# wake_on_sleep.net
KiCad netlist of a schematic drawn in EAGLE
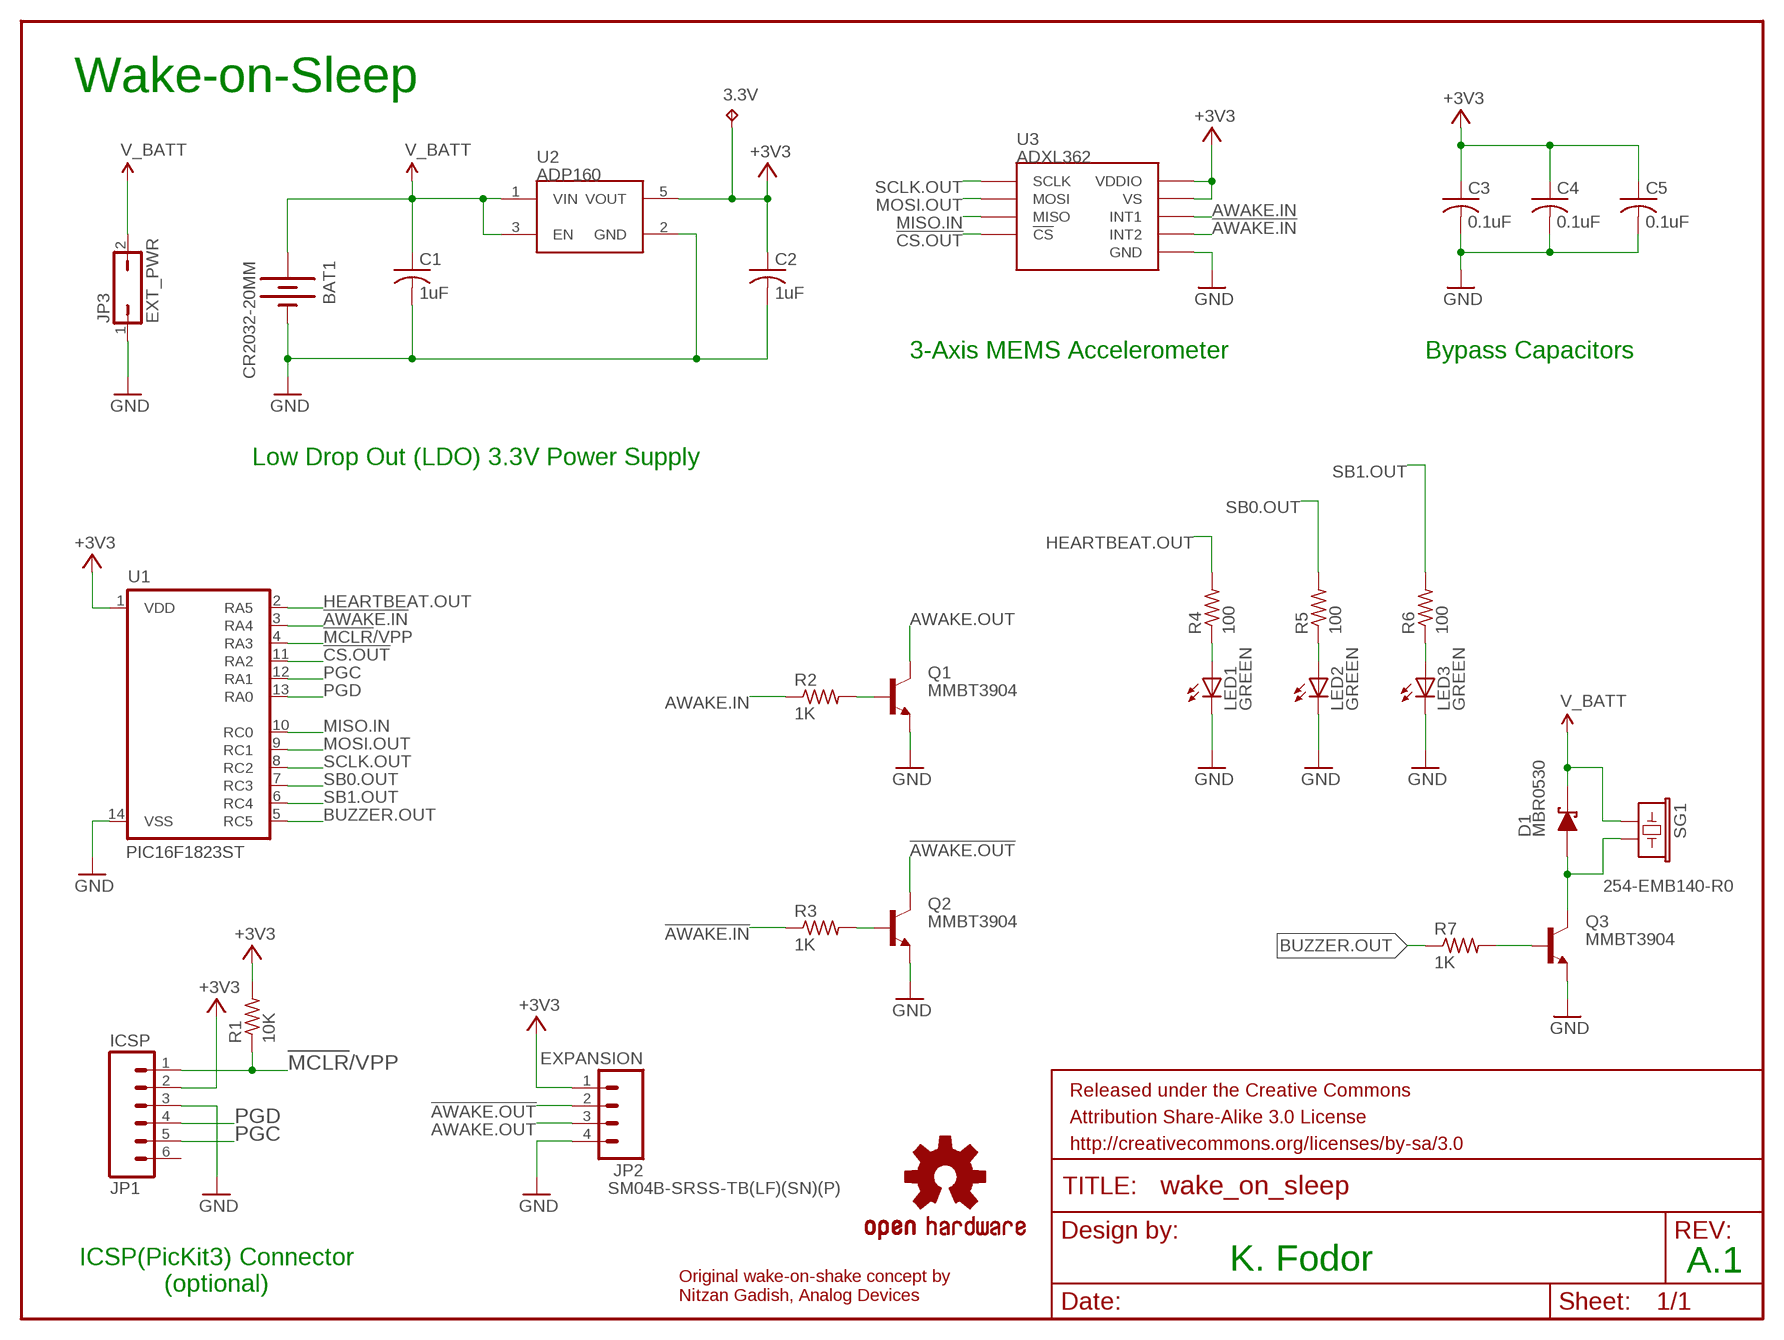
[diagram p0: schematic, sheet 1]

(export (version "E")
  (design (tool "Eeschema 10.0.6"))
  (components
    (comp (ref "3.3V")
      (value "TPB2,54")
      (footprint "eagle-import:B2,54")
      (fields (field (name "TP_SIGNAL_NAME") "+3V3"))
      (libsource (lib "eagle-import") (part "TPB2,54"))
    )
    (comp (ref "BAT1")
      (value "CR2032-20MM")
      (footprint "eagle-import:BATTCON_20MM_SMD_EJECT")
      (fields (field (name "PARTNO") "BA2032SM"))
      (libsource (lib "eagle-import") (part "BATTERY20MM_SMD"))
    )
    (comp (ref "C1")
      (value "1uF")
      (footprint "eagle-import:C0603")
      (fields (field (name "PARTNO") "C0603C105K8RACTU"))
      (libsource (lib "eagle-import") (part "C-USC0603"))
    )
    (comp (ref "C2")
      (value "1uF")
      (footprint "eagle-import:C0603")
      (fields (field (name "PARTNO") "C0603C105K8RACTU"))
      (libsource (lib "eagle-import") (part "C-USC0603"))
    )
    (comp (ref "C3")
      (value "0.1uF")
      (footprint "eagle-import:C0603")
      (fields (field (name "PARTNO") "C0603C104M4RACTU"))
      (libsource (lib "eagle-import") (part "C-USC0603"))
    )
    (comp (ref "C4")
      (value "0.1uF")
      (footprint "eagle-import:C0603")
      (fields (field (name "PARTNO") "C0603C104M4RACTU"))
      (libsource (lib "eagle-import") (part "C-USC0603"))
    )
    (comp (ref "C5")
      (value "0.1uF")
      (footprint "eagle-import:C0603")
      (fields (field (name "PARTNO") "C0603C104M4RACTU"))
      (libsource (lib "eagle-import") (part "C-USC0603"))
    )
    (comp (ref "D1")
      (value "MBR0530")
      (footprint "eagle-import:SOD-123")
      (libsource (lib "eagle-import") (part "D_SCHOTTKYK"))
    )
    (comp (ref "FRAME1")
      (value "FRAME-LETTER")
      (footprint "eagle-import:CREATIVE_COMMONS")
      (fields (field (name "BOM") "EXCLUDE"))
      (libsource (lib "eagle-import") (part "FRAME-LETTER"))
    )
    (comp (ref "JP1")
      (value "ICSP")
      (footprint "eagle-import:1X06_SMD_MALE")
      (fields (field (name "PARTNO") "5-146128-4"))
      (libsource (lib "eagle-import") (part "M06SMD_MALE"))
    )
    (comp (ref "JP2")
      (value "EXPANSION")
      (footprint "eagle-import:1X04-1MM-RA")
      (fields (field (name "PARTNO") "SM04B-SRSS-TB(LF)(SN)(P)"))
      (libsource (lib "eagle-import") (part "M04SMD2"))
    )
    (comp (ref "JP3")
      (value "EXT_PWR")
      (footprint "eagle-import:JP1")
      (fields (field (name "PARTNO") "826936-2"))
      (libsource (lib "eagle-import") (part "JP1Q"))
    )
    (comp (ref "LED1")
      (value "GREEN")
      (footprint "eagle-import:CHIPLED_0603")
      (fields (field (name "PARTNO") "LTST-C191KGKT"))
      (libsource (lib "eagle-import") (part "LEDCHIPLED_0603"))
    )
    (comp (ref "LED2")
      (value "GREEN")
      (footprint "eagle-import:CHIPLED_0603")
      (fields (field (name "PARTNO") "LTST-C191KGKT"))
      (libsource (lib "eagle-import") (part "LEDCHIPLED_0603"))
    )
    (comp (ref "LED3")
      (value "GREEN")
      (footprint "eagle-import:CHIPLED_0603")
      (fields (field (name "PARTNO") "LTST-C191KGKT"))
      (libsource (lib "eagle-import") (part "LEDCHIPLED_0603"))
    )
    (comp (ref "LOGO1")
      (value "OSHW-LOGOL")
      (footprint "eagle-import:OSHW-LOGO-L")
      (libsource (lib "eagle-import") (part "OSHW-LOGOL"))
    )
    (comp (ref "Q1")
      (value "MMBT3904")
      (footprint "eagle-import:SOT23")
      (libsource (lib "eagle-import") (part "TRANSISTOR_NPNSOT23"))
    )
    (comp (ref "Q2")
      (value "MMBT3904")
      (footprint "eagle-import:SOT23")
      (libsource (lib "eagle-import") (part "TRANSISTOR_NPNSOT23"))
    )
    (comp (ref "Q3")
      (value "MMBT3904")
      (footprint "eagle-import:SOT23")
      (libsource (lib "eagle-import") (part "TRANSISTOR_NPNSOT23"))
    )
    (comp (ref "R1")
      (value "10K")
      (footprint "eagle-import:R0603R")
      (fields (field (name "PARTNO") "RK73H1JTTD1002F"))
      (libsource (lib "eagle-import") (part "R-US_R0603R"))
    )
    (comp (ref "R2")
      (value "1K")
      (footprint "eagle-import:R0603R")
      (fields (field (name "PARTNO") "RK73H1JTTD1001F"))
      (libsource (lib "eagle-import") (part "R-US_R0603R"))
    )
    (comp (ref "R3")
      (value "1K")
      (footprint "eagle-import:R0603R")
      (fields (field (name "PARTNO") "RK73H1JTTD1001F"))
      (libsource (lib "eagle-import") (part "R-US_R0603R"))
    )
    (comp (ref "R4")
      (value "100")
      (footprint "eagle-import:R0603R")
      (fields (field (name "PARTNO") "RK73H1JTTD1000F"))
      (libsource (lib "eagle-import") (part "R-US_R0603R"))
    )
    (comp (ref "R5")
      (value "100")
      (footprint "eagle-import:R0603R")
      (fields (field (name "PARTNO") "RK73H1JTTD1000F"))
      (libsource (lib "eagle-import") (part "R-US_R0603R"))
    )
    (comp (ref "R6")
      (value "100")
      (footprint "eagle-import:R0603R")
      (fields (field (name "PARTNO") "RK73H1JTTD1000F"))
      (libsource (lib "eagle-import") (part "R-US_R0603R"))
    )
    (comp (ref "R7")
      (value "1K")
      (footprint "eagle-import:R0603R")
      (fields (field (name "PARTNO") "RK73H1JTTD1001F"))
      (libsource (lib "eagle-import") (part "R-US_R0603R"))
    )
    (comp (ref "SG1")
      (value "BUZZERPTH")
      (footprint "eagle-import:BUZZER-12MM")
      (fields (field (name "PARTNO") "254-EMB140-R0"))
      (libsource (lib "eagle-import") (part "BUZZERPTH"))
    )
    (comp (ref "U1")
      (value "PIC16F1823ST")
      (footprint "eagle-import:TSSOP14")
      (fields (field (name "PARTNO") "PIC16F1823-I/ST"))
      (libsource (lib "eagle-import") (part "PIC16F1823ST"))
    )
    (comp (ref "U2")
      (value "ADP160")
      (footprint "eagle-import:SOT23-5")
      (fields (field (name "PARTNO") "ADP160AUJZ-3.3-R7"))
      (libsource (lib "eagle-import") (part "ADP160"))
    )
    (comp (ref "U3")
      (value "ADXL362")
      (footprint "eagle-import:ADXL362_EXT")
      (fields (field (name "PARTNO") "ADXL362BCCZ-RL"))
      (libsource (lib "eagle-import") (part "ADXL362EXT"))
    )
  )
  (nets
    (net (code "1") (name "+3V3") (class "Default")
      (node (ref "3.3V") (pin "TP") (pinfunction "TP_TP") (pintype "input"))
      (node (ref "C2") (pin "1") (pinfunction "1_1") (pintype "passive"))
      (node (ref "C3") (pin "1") (pinfunction "1_1") (pintype "passive"))
      (node (ref "C4") (pin "1") (pinfunction "1_1") (pintype "passive"))
      (node (ref "C5") (pin "1") (pinfunction "1_1") (pintype "passive"))
      (node (ref "JP1") (pin "2") (pinfunction "2_2") (pintype "passive"))
      (node (ref "JP2") (pin "1") (pinfunction "1_1") (pintype "passive"))
      (node (ref "R1") (pin "2") (pinfunction "2_2") (pintype "passive"))
      (node (ref "U1") (pin "1") (pinfunction "VDD_1") (pintype "power_in"))
      (node (ref "U2") (pin "5") (pinfunction "VOUT_5") (pintype "bidirectional"))
      (node (ref "U3") (pin "P$1") (pinfunction "VDDIO_P$1") (pintype "bidirectional"))
      (node (ref "U3") (pin "P$14") (pinfunction "VS_P$14") (pintype "bidirectional"))
    )
    (net (code "2") (name "/AWAKE.IN") (class "Default")
      (node (ref "R2") (pin "1") (pinfunction "1_1") (pintype "passive"))
      (node (ref "U3") (pin "P$11") (pinfunction "INT1_P$11") (pintype "bidirectional"))
    )
    (net (code "3") (name "/AWAKE.OUT") (class "Default")
      (node (ref "JP2") (pin "3") (pinfunction "3_3") (pintype "passive"))
      (node (ref "Q1") (pin "3") (pinfunction "C_3") (pintype "passive"))
    )
    (net (code "4") (name "/HEARTBEAT.OUT") (class "Default")
      (node (ref "R4") (pin "2") (pinfunction "2_2") (pintype "passive"))
      (node (ref "U1") (pin "2") (pinfunction "RA5_2") (pintype "bidirectional"))
    )
    (net (code "5") (name "/MISO.IN") (class "Default")
      (node (ref "U1") (pin "10") (pinfunction "RC0_10") (pintype "bidirectional"))
      (node (ref "U3") (pin "P$7") (pinfunction "MISO_P$7") (pintype "bidirectional"))
    )
    (net (code "6") (name "/MOSI.OUT") (class "Default")
      (node (ref "U1") (pin "9") (pinfunction "RC1_9") (pintype "bidirectional"))
      (node (ref "U3") (pin "P$6") (pinfunction "MOSI_P$6") (pintype "bidirectional"))
    )
    (net (code "7") (name "/PGC") (class "Default")
      (node (ref "JP1") (pin "5") (pinfunction "5_5") (pintype "passive"))
      (node (ref "U1") (pin "12") (pinfunction "RA1_12") (pintype "bidirectional"))
    )
    (net (code "8") (name "/PGD") (class "Default")
      (node (ref "JP1") (pin "4") (pinfunction "4_4") (pintype "passive"))
      (node (ref "U1") (pin "13") (pinfunction "RA0_13") (pintype "bidirectional"))
    )
    (net (code "9") (name "/SB0.OUT") (class "Default")
      (node (ref "R5") (pin "2") (pinfunction "2_2") (pintype "passive"))
      (node (ref "U1") (pin "7") (pinfunction "RC3_7") (pintype "bidirectional"))
    )
    (net (code "10") (name "/SB1.OUT") (class "Default")
      (node (ref "R6") (pin "2") (pinfunction "2_2") (pintype "passive"))
      (node (ref "U1") (pin "6") (pinfunction "RC4_6") (pintype "bidirectional"))
    )
    (net (code "11") (name "/SCLK.OUT") (class "Default")
      (node (ref "U1") (pin "8") (pinfunction "RC2_8") (pintype "bidirectional"))
      (node (ref "U3") (pin "P$4") (pinfunction "SCLK_P$4") (pintype "bidirectional"))
    )
    (net (code "12") (name "/~{AWAKE.IN}") (class "Default")
      (node (ref "R3") (pin "1") (pinfunction "1_1") (pintype "passive"))
      (node (ref "U1") (pin "3") (pinfunction "RA4_3") (pintype "bidirectional"))
      (node (ref "U3") (pin "P$9") (pinfunction "INT2_P$9") (pintype "bidirectional"))
    )
    (net (code "13") (name "/~{AWAKE.OUT}") (class "Default")
      (node (ref "JP2") (pin "2") (pinfunction "2_2") (pintype "passive"))
      (node (ref "Q2") (pin "3") (pinfunction "C_3") (pintype "passive"))
    )
    (net (code "14") (name "/~{CS.OUT}") (class "Default")
      (node (ref "U1") (pin "11") (pinfunction "RA2_11") (pintype "bidirectional"))
      (node (ref "U3") (pin "P$8") (pinfunction "~{CS}_P$8") (pintype "bidirectional"))
    )
    (net (code "15") (name "/~{MCLR}{slash}VPP") (class "Default")
      (node (ref "JP1") (pin "1") (pinfunction "1_1") (pintype "passive"))
      (node (ref "R1") (pin "1") (pinfunction "1_1") (pintype "passive"))
      (node (ref "U1") (pin "4") (pinfunction "RA3_4") (pintype "input"))
    )
    (net (code "16") (name "BUZZER.OUT") (class "Default")
      (node (ref "R7") (pin "1") (pinfunction "1_1") (pintype "passive"))
      (node (ref "U1") (pin "5") (pinfunction "RC5_5") (pintype "bidirectional"))
    )
    (net (code "17") (name "GND") (class "Default")
      (node (ref "BAT1") (pin "VCC@2") (pinfunction "-_VCC@2") (pintype "power_in"))
      (node (ref "C1") (pin "2") (pinfunction "2_2") (pintype "passive"))
      (node (ref "C2") (pin "2") (pinfunction "2_2") (pintype "passive"))
      (node (ref "C3") (pin "2") (pinfunction "2_2") (pintype "passive"))
      (node (ref "C4") (pin "2") (pinfunction "2_2") (pintype "passive"))
      (node (ref "C5") (pin "2") (pinfunction "2_2") (pintype "passive"))
      (node (ref "JP1") (pin "3") (pinfunction "3_3") (pintype "passive"))
      (node (ref "JP2") (pin "4") (pinfunction "4_4") (pintype "passive"))
      (node (ref "JP3") (pin "1") (pinfunction "1_1") (pintype "passive"))
      (node (ref "LED1") (pin "C") (pinfunction "C_C") (pintype "passive"))
      (node (ref "LED2") (pin "C") (pinfunction "C_C") (pintype "passive"))
      (node (ref "LED3") (pin "C") (pinfunction "C_C") (pintype "passive"))
      (node (ref "Q1") (pin "2") (pinfunction "E_2") (pintype "passive"))
      (node (ref "Q2") (pin "2") (pinfunction "E_2") (pintype "passive"))
      (node (ref "Q3") (pin "2") (pinfunction "E_2") (pintype "passive"))
      (node (ref "U1") (pin "14") (pinfunction "VSS_14") (pintype "power_in"))
      (node (ref "U2") (pin "2") (pinfunction "GND_2") (pintype "bidirectional"))
      (node (ref "U3") (pin "P$12") (pinfunction "GND_P$12") (pintype "bidirectional"))
      (node (ref "U3") (pin "P$13") (pinfunction "GND_P$13") (pintype "bidirectional"))
      (node (ref "U3") (pin "P$16") (pinfunction "GND_P$16") (pintype "bidirectional"))
    )
    (net (code "18") (name "Net-(LED1-PadA)") (class "Default")
      (node (ref "LED1") (pin "A") (pinfunction "A_A") (pintype "passive"))
      (node (ref "R4") (pin "1") (pinfunction "1_1") (pintype "passive"))
    )
    (net (code "19") (name "Net-(LED2-PadA)") (class "Default")
      (node (ref "LED2") (pin "A") (pinfunction "A_A") (pintype "passive"))
      (node (ref "R5") (pin "1") (pinfunction "1_1") (pintype "passive"))
    )
    (net (code "20") (name "Net-(LED3-PadA)") (class "Default")
      (node (ref "LED3") (pin "A") (pinfunction "A_A") (pintype "passive"))
      (node (ref "R6") (pin "1") (pinfunction "1_1") (pintype "passive"))
    )
    (net (code "21") (name "Net-(Q1-B)") (class "Default")
      (node (ref "Q1") (pin "1") (pinfunction "B_1") (pintype "passive"))
      (node (ref "R2") (pin "2") (pinfunction "2_2") (pintype "passive"))
    )
    (net (code "22") (name "Net-(Q2-B)") (class "Default")
      (node (ref "Q2") (pin "1") (pinfunction "B_1") (pintype "passive"))
      (node (ref "R3") (pin "2") (pinfunction "2_2") (pintype "passive"))
    )
    (net (code "23") (name "Net-(Q3-B)") (class "Default")
      (node (ref "Q3") (pin "1") (pinfunction "B_1") (pintype "passive"))
      (node (ref "R7") (pin "2") (pinfunction "2_2") (pintype "passive"))
    )
    (net (code "24") (name "Net-(Q3-C)") (class "Default")
      (node (ref "D1") (pin "A") (pinfunction "A_A") (pintype "passive"))
      (node (ref "Q3") (pin "3") (pinfunction "C_3") (pintype "passive"))
      (node (ref "SG1") (pin "-") (pinfunction "2_-") (pintype "passive"))
    )
    (net (code "25") (name "V_BATT") (class "Default")
      (node (ref "BAT1") (pin "VCC@1") (pinfunction "+_VCC@1") (pintype "power_in"))
      (node (ref "C1") (pin "1") (pinfunction "1_1") (pintype "passive"))
      (node (ref "D1") (pin "C") (pinfunction "C_C") (pintype "passive"))
      (node (ref "JP3") (pin "2") (pinfunction "2_2") (pintype "passive"))
      (node (ref "SG1") (pin "+") (pinfunction "1_+") (pintype "passive"))
      (node (ref "U2") (pin "1") (pinfunction "VIN_1") (pintype "bidirectional"))
      (node (ref "U2") (pin "3") (pinfunction "EN_3") (pintype "bidirectional"))
    )
    (net (code "26") (name "unconnected-(JP1-Pad6)") (class "Default")
      (node (ref "JP1") (pin "6") (pinfunction "6_6") (pintype "passive"))
    )
  )
)
